# piezo-driver_v0_1-R001.net
KiCad netlist of a schematic drawn in EAGLE
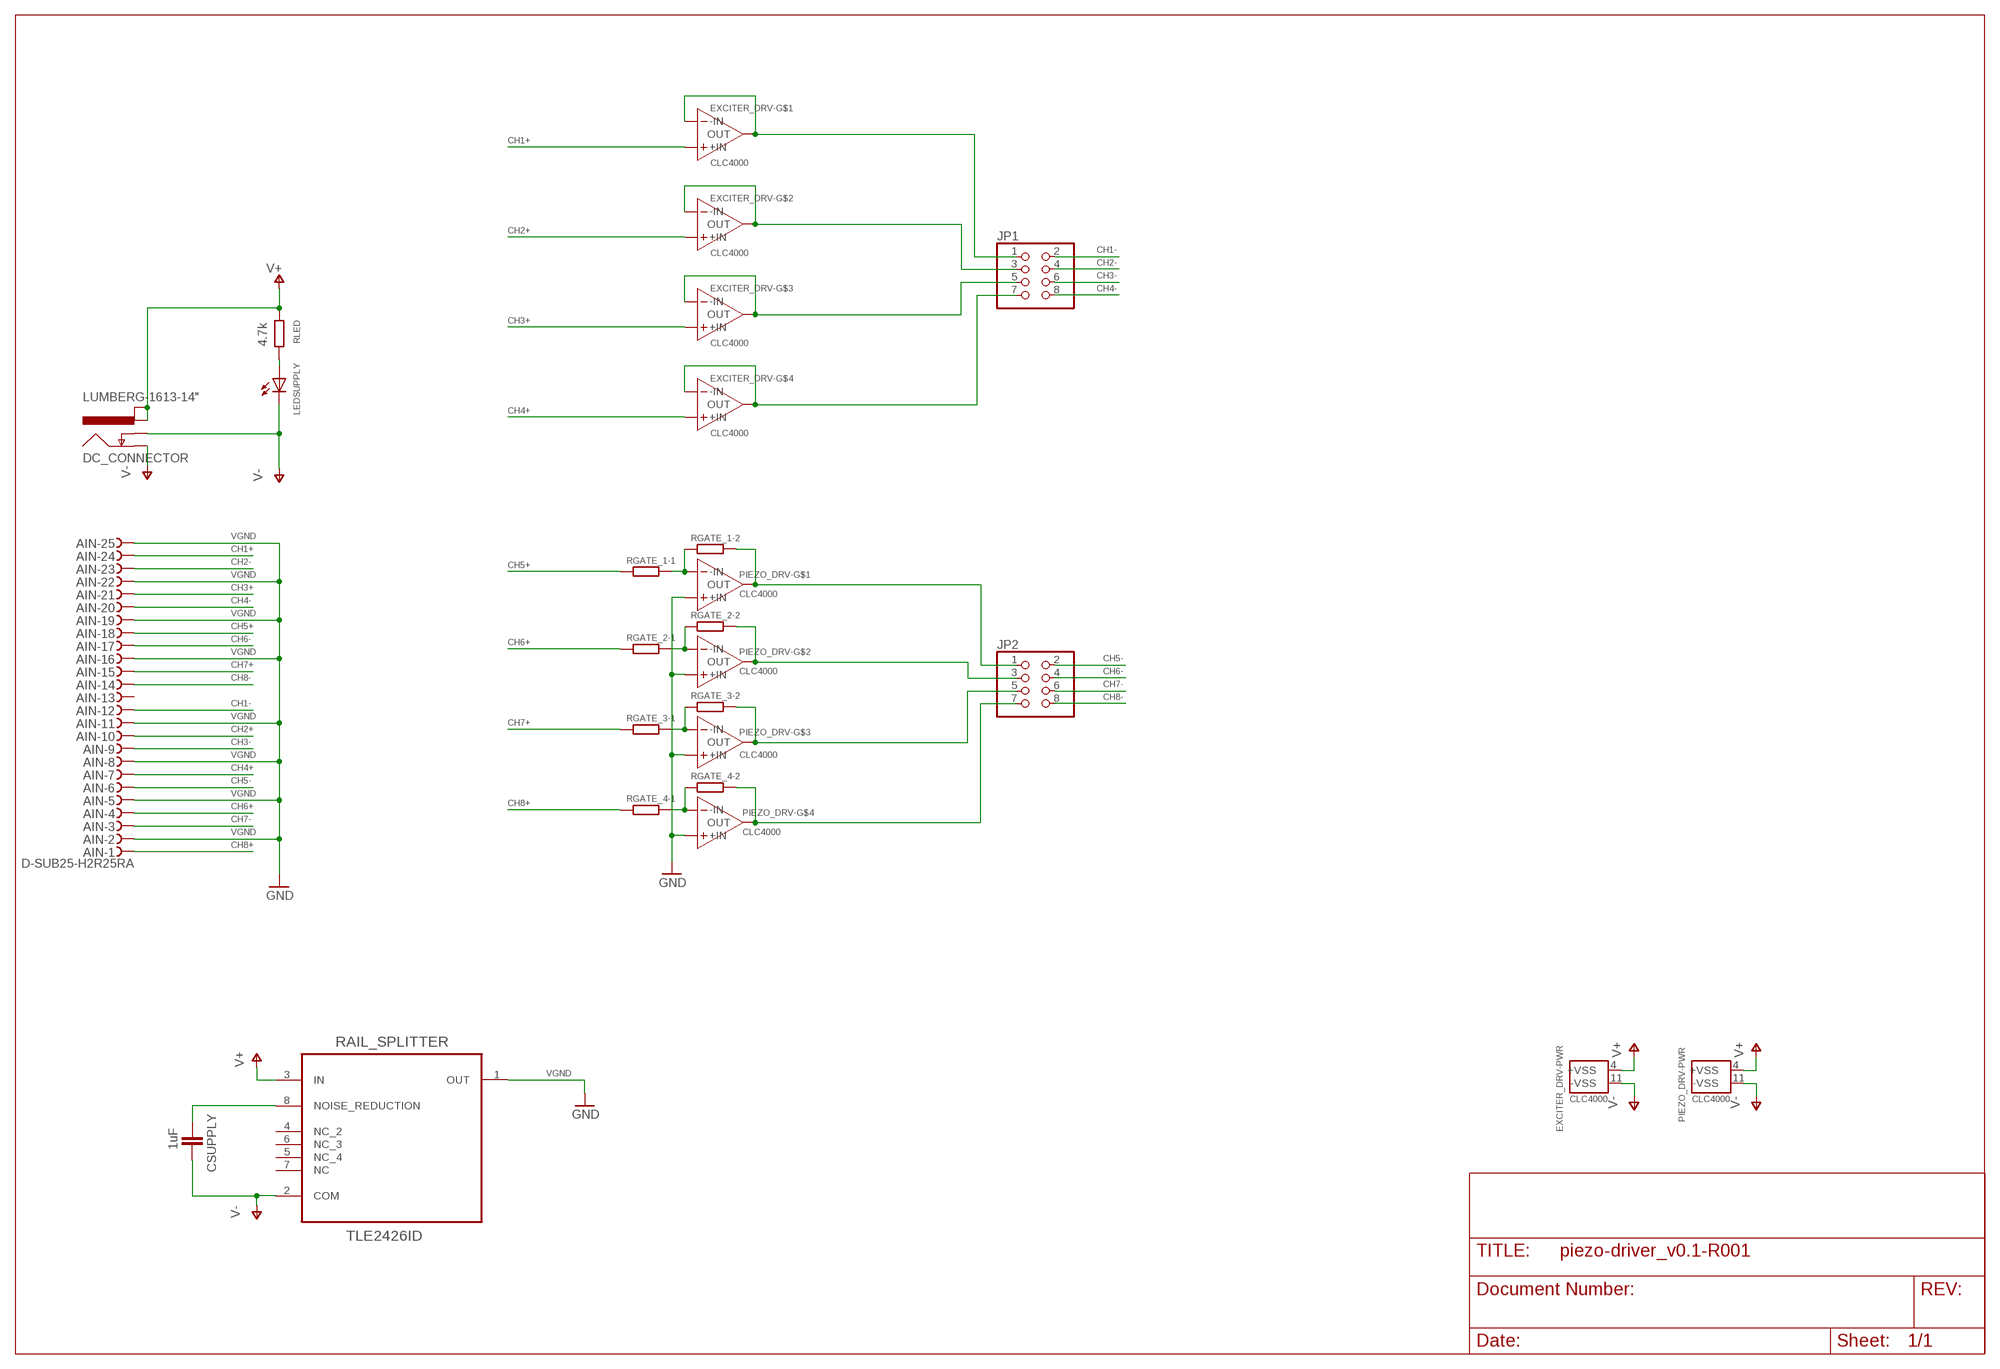
[diagram p0: schematic, sheet 1]

(export (version "E")
  (design (tool "Eeschema 10.0.6"))
  (components
    (comp (ref "AIN")
      (value "D-SUB25-H2R25RA")
      (footprint "eagle-import:H2R25RA")
      (libsource (lib "eagle-import") (part "D-SUB25-H2R25RA"))
    )
    (comp (ref "CSUPPLY")
      (value "1uF")
      (footprint "eagle-import:C0603")
      (libsource (lib "eagle-import") (part "C-EUC0603"))
    )
    (comp (ref "DC_CONNECTOR")
      (value "LUMBERG-1613-14\"")
      (footprint "eagle-import:LUMBERG-1613_14")
      (libsource (lib "eagle-import") (part "LUMBERG-1613-14{dblquote}"))
    )
    (comp (ref "EXCITER_DRV")
      (value "CLC4000")
      (footprint "eagle-import:SOIC-14")
      (libsource (lib "eagle-import") (part "CLC4000"))
    )
    (comp (ref "JP1")
      (value "PINHD-2X4/90")
      (footprint "eagle-import:2X04_90")
      (libsource (lib "eagle-import") (part "PINHD-2X4/90"))
    )
    (comp (ref "JP2")
      (value "PINHD-2X4/90")
      (footprint "eagle-import:2X04_90")
      (libsource (lib "eagle-import") (part "PINHD-2X4/90"))
    )
    (comp (ref "LEDSUPPLY")
      (value "LED3MM")
      (footprint "eagle-import:LED3MM")
      (libsource (lib "eagle-import") (part "LED3MM"))
    )
    (comp (ref "PIEZO_DRV")
      (value "CLC4000")
      (footprint "eagle-import:SOIC-14")
      (libsource (lib "eagle-import") (part "CLC4000"))
    )
    (comp (ref "RAIL_SPLITTER")
      (value "TLE2426ID")
      (footprint "eagle-import:SOIC127P600X175-8N")
      (libsource (lib "eagle-import") (part "TLE2426ID"))
    )
    (comp (ref "RGATE_1-1")
      (value "R-EU_R0805")
      (footprint "eagle-import:R0805")
      (libsource (lib "eagle-import") (part "R-EU_R0805"))
    )
    (comp (ref "RGATE_1-2")
      (value "R-EU_R0805")
      (footprint "eagle-import:R0805")
      (libsource (lib "eagle-import") (part "R-EU_R0805"))
    )
    (comp (ref "RGATE_2-1")
      (value "R-EU_R0805")
      (footprint "eagle-import:R0805")
      (libsource (lib "eagle-import") (part "R-EU_R0805"))
    )
    (comp (ref "RGATE_2-2")
      (value "R-EU_R0805")
      (footprint "eagle-import:R0805")
      (libsource (lib "eagle-import") (part "R-EU_R0805"))
    )
    (comp (ref "RGATE_3-1")
      (value "R-EU_R0805")
      (footprint "eagle-import:R0805")
      (libsource (lib "eagle-import") (part "R-EU_R0805"))
    )
    (comp (ref "RGATE_3-2")
      (value "R-EU_R0805")
      (footprint "eagle-import:R0805")
      (libsource (lib "eagle-import") (part "R-EU_R0805"))
    )
    (comp (ref "RGATE_4-1")
      (value "R-EU_R0805")
      (footprint "eagle-import:R0805")
      (libsource (lib "eagle-import") (part "R-EU_R0805"))
    )
    (comp (ref "RGATE_4-2")
      (value "R-EU_R0805")
      (footprint "eagle-import:R0805")
      (libsource (lib "eagle-import") (part "R-EU_R0805"))
    )
    (comp (ref "RLED")
      (value "4.7k")
      (footprint "eagle-import:R0805")
      (libsource (lib "eagle-import") (part "R-EU_R0805"))
    )
  )
  (nets
    (net (code "1") (name "/CH1+") (class "Default")
      (node (ref "AIN") (pin "24") (pinfunction "F_24") (pintype "passive"))
      (node (ref "EXCITER_DRV") (pin "3") (pinfunction "+IN_3") (pintype "bidirectional"))
    )
    (net (code "2") (name "/CH1-") (class "Default")
      (node (ref "AIN") (pin "12") (pinfunction "F_12") (pintype "passive"))
      (node (ref "JP1") (pin "2") (pinfunction "2_2") (pintype "passive"))
    )
    (net (code "3") (name "/CH2+") (class "Default")
      (node (ref "AIN") (pin "10") (pinfunction "F_10") (pintype "passive"))
      (node (ref "EXCITER_DRV") (pin "5") (pinfunction "+IN_5") (pintype "bidirectional"))
    )
    (net (code "4") (name "/CH2-") (class "Default")
      (node (ref "AIN") (pin "23") (pinfunction "F_23") (pintype "passive"))
      (node (ref "JP1") (pin "4") (pinfunction "4_4") (pintype "passive"))
    )
    (net (code "5") (name "/CH3+") (class "Default")
      (node (ref "AIN") (pin "21") (pinfunction "F_21") (pintype "passive"))
      (node (ref "EXCITER_DRV") (pin "10") (pinfunction "+IN_10") (pintype "bidirectional"))
    )
    (net (code "6") (name "/CH3-") (class "Default")
      (node (ref "AIN") (pin "9") (pinfunction "F_9") (pintype "passive"))
      (node (ref "JP1") (pin "6") (pinfunction "6_6") (pintype "passive"))
    )
    (net (code "7") (name "/CH4+") (class "Default")
      (node (ref "AIN") (pin "7") (pinfunction "F_7") (pintype "passive"))
      (node (ref "EXCITER_DRV") (pin "12") (pinfunction "+IN_12") (pintype "bidirectional"))
    )
    (net (code "8") (name "/CH4-") (class "Default")
      (node (ref "AIN") (pin "20") (pinfunction "F_20") (pintype "passive"))
      (node (ref "JP1") (pin "8") (pinfunction "8_8") (pintype "passive"))
    )
    (net (code "9") (name "/CH5+") (class "Default")
      (node (ref "AIN") (pin "18") (pinfunction "F_18") (pintype "passive"))
      (node (ref "RGATE_1-1") (pin "1") (pinfunction "1_1") (pintype "passive"))
    )
    (net (code "10") (name "/CH5-") (class "Default")
      (node (ref "AIN") (pin "6") (pinfunction "F_6") (pintype "passive"))
      (node (ref "JP2") (pin "2") (pinfunction "2_2") (pintype "passive"))
    )
    (net (code "11") (name "/CH6+") (class "Default")
      (node (ref "AIN") (pin "4") (pinfunction "F_4") (pintype "passive"))
      (node (ref "RGATE_2-1") (pin "1") (pinfunction "1_1") (pintype "passive"))
    )
    (net (code "12") (name "/CH6-") (class "Default")
      (node (ref "AIN") (pin "17") (pinfunction "F_17") (pintype "passive"))
      (node (ref "JP2") (pin "4") (pinfunction "4_4") (pintype "passive"))
    )
    (net (code "13") (name "/CH7+") (class "Default")
      (node (ref "AIN") (pin "15") (pinfunction "F_15") (pintype "passive"))
      (node (ref "RGATE_3-1") (pin "1") (pinfunction "1_1") (pintype "passive"))
    )
    (net (code "14") (name "/CH7-") (class "Default")
      (node (ref "AIN") (pin "3") (pinfunction "F_3") (pintype "passive"))
      (node (ref "JP2") (pin "6") (pinfunction "6_6") (pintype "passive"))
    )
    (net (code "15") (name "/CH8+") (class "Default")
      (node (ref "AIN") (pin "1") (pinfunction "F_1") (pintype "passive"))
      (node (ref "RGATE_4-1") (pin "1") (pinfunction "1_1") (pintype "passive"))
    )
    (net (code "16") (name "/CH8-") (class "Default")
      (node (ref "AIN") (pin "14") (pinfunction "F_14") (pintype "passive"))
      (node (ref "JP2") (pin "8") (pinfunction "8_8") (pintype "passive"))
    )
    (net (code "17") (name "GND") (class "Default")
      (node (ref "AIN") (pin "11") (pinfunction "F_11") (pintype "passive"))
      (node (ref "AIN") (pin "16") (pinfunction "F_16") (pintype "passive"))
      (node (ref "AIN") (pin "19") (pinfunction "F_19") (pintype "passive"))
      (node (ref "AIN") (pin "2") (pinfunction "F_2") (pintype "passive"))
      (node (ref "AIN") (pin "22") (pinfunction "F_22") (pintype "passive"))
      (node (ref "AIN") (pin "25") (pinfunction "F_25") (pintype "passive"))
      (node (ref "AIN") (pin "5") (pinfunction "F_5") (pintype "passive"))
      (node (ref "AIN") (pin "8") (pinfunction "F_8") (pintype "passive"))
      (node (ref "PIEZO_DRV") (pin "10") (pinfunction "+IN_10") (pintype "bidirectional"))
      (node (ref "PIEZO_DRV") (pin "12") (pinfunction "+IN_12") (pintype "bidirectional"))
      (node (ref "PIEZO_DRV") (pin "3") (pinfunction "+IN_3") (pintype "bidirectional"))
      (node (ref "PIEZO_DRV") (pin "5") (pinfunction "+IN_5") (pintype "bidirectional"))
      (node (ref "RAIL_SPLITTER") (pin "1") (pinfunction "OUT_1") (pintype "output"))
    )
    (net (code "18") (name "Net-(EXCITER_DRVA--IN)") (class "Default")
      (node (ref "EXCITER_DRV") (pin "1") (pinfunction "OUT_1") (pintype "bidirectional"))
      (node (ref "EXCITER_DRV") (pin "2") (pinfunction "-IN_2") (pintype "bidirectional"))
      (node (ref "JP1") (pin "1") (pinfunction "1_1") (pintype "passive"))
    )
    (net (code "19") (name "Net-(EXCITER_DRVB--IN)") (class "Default")
      (node (ref "EXCITER_DRV") (pin "6") (pinfunction "-IN_6") (pintype "bidirectional"))
      (node (ref "EXCITER_DRV") (pin "7") (pinfunction "OUT_7") (pintype "bidirectional"))
      (node (ref "JP1") (pin "3") (pinfunction "3_3") (pintype "passive"))
    )
    (net (code "20") (name "Net-(EXCITER_DRVC--IN)") (class "Default")
      (node (ref "EXCITER_DRV") (pin "8") (pinfunction "OUT_8") (pintype "bidirectional"))
      (node (ref "EXCITER_DRV") (pin "9") (pinfunction "-IN_9") (pintype "bidirectional"))
      (node (ref "JP1") (pin "5") (pinfunction "5_5") (pintype "passive"))
    )
    (net (code "21") (name "Net-(EXCITER_DRVD--IN)") (class "Default")
      (node (ref "EXCITER_DRV") (pin "13") (pinfunction "-IN_13") (pintype "bidirectional"))
      (node (ref "EXCITER_DRV") (pin "14") (pinfunction "OUT_14") (pintype "bidirectional"))
      (node (ref "JP1") (pin "7") (pinfunction "7_7") (pintype "passive"))
    )
    (net (code "22") (name "Net-(LEDSUPPLY-PadA)") (class "Default")
      (node (ref "LEDSUPPLY") (pin "A") (pinfunction "A_A") (pintype "passive"))
      (node (ref "RLED") (pin "1") (pinfunction "1_1") (pintype "passive"))
    )
    (net (code "23") (name "Net-(PIEZO_DRVA--IN)") (class "Default")
      (node (ref "PIEZO_DRV") (pin "2") (pinfunction "-IN_2") (pintype "bidirectional"))
      (node (ref "RGATE_1-1") (pin "2") (pinfunction "2_2") (pintype "passive"))
      (node (ref "RGATE_1-2") (pin "1") (pinfunction "1_1") (pintype "passive"))
    )
    (net (code "24") (name "Net-(PIEZO_DRVA-OUT)") (class "Default")
      (node (ref "JP2") (pin "1") (pinfunction "1_1") (pintype "passive"))
      (node (ref "PIEZO_DRV") (pin "1") (pinfunction "OUT_1") (pintype "bidirectional"))
      (node (ref "RGATE_1-2") (pin "2") (pinfunction "2_2") (pintype "passive"))
    )
    (net (code "25") (name "Net-(PIEZO_DRVB--IN)") (class "Default")
      (node (ref "PIEZO_DRV") (pin "6") (pinfunction "-IN_6") (pintype "bidirectional"))
      (node (ref "RGATE_2-1") (pin "2") (pinfunction "2_2") (pintype "passive"))
      (node (ref "RGATE_2-2") (pin "1") (pinfunction "1_1") (pintype "passive"))
    )
    (net (code "26") (name "Net-(PIEZO_DRVB-OUT)") (class "Default")
      (node (ref "JP2") (pin "3") (pinfunction "3_3") (pintype "passive"))
      (node (ref "PIEZO_DRV") (pin "7") (pinfunction "OUT_7") (pintype "bidirectional"))
      (node (ref "RGATE_2-2") (pin "2") (pinfunction "2_2") (pintype "passive"))
    )
    (net (code "27") (name "Net-(PIEZO_DRVC--IN)") (class "Default")
      (node (ref "PIEZO_DRV") (pin "9") (pinfunction "-IN_9") (pintype "bidirectional"))
      (node (ref "RGATE_3-1") (pin "2") (pinfunction "2_2") (pintype "passive"))
      (node (ref "RGATE_3-2") (pin "1") (pinfunction "1_1") (pintype "passive"))
    )
    (net (code "28") (name "Net-(PIEZO_DRVC-OUT)") (class "Default")
      (node (ref "JP2") (pin "5") (pinfunction "5_5") (pintype "passive"))
      (node (ref "PIEZO_DRV") (pin "8") (pinfunction "OUT_8") (pintype "bidirectional"))
      (node (ref "RGATE_3-2") (pin "2") (pinfunction "2_2") (pintype "passive"))
    )
    (net (code "29") (name "Net-(PIEZO_DRVD--IN)") (class "Default")
      (node (ref "PIEZO_DRV") (pin "13") (pinfunction "-IN_13") (pintype "bidirectional"))
      (node (ref "RGATE_4-1") (pin "2") (pinfunction "2_2") (pintype "passive"))
      (node (ref "RGATE_4-2") (pin "1") (pinfunction "1_1") (pintype "passive"))
    )
    (net (code "30") (name "Net-(PIEZO_DRVD-OUT)") (class "Default")
      (node (ref "JP2") (pin "7") (pinfunction "7_7") (pintype "passive"))
      (node (ref "PIEZO_DRV") (pin "14") (pinfunction "OUT_14") (pintype "bidirectional"))
      (node (ref "RGATE_4-2") (pin "2") (pinfunction "2_2") (pintype "passive"))
    )
    (net (code "31") (name "Net-(RAIL_SPLITTER-NOISE_REDUCTION)") (class "Default")
      (node (ref "CSUPPLY") (pin "1") (pinfunction "1_1") (pintype "passive"))
      (node (ref "RAIL_SPLITTER") (pin "8") (pinfunction "NOISE_REDUCTION_8") (pintype "passive"))
    )
    (net (code "32") (name "V+") (class "Default")
      (node (ref "DC_CONNECTOR") (pin "3") (pinfunction "PWR_1_3") (pintype "power_in"))
      (node (ref "DC_CONNECTOR") (pin "4") (pinfunction "PWR_2_4") (pintype "power_in"))
      (node (ref "EXCITER_DRV") (pin "4") (pinfunction "+VSS_4") (pintype "power_in"))
      (node (ref "PIEZO_DRV") (pin "4") (pinfunction "+VSS_4") (pintype "power_in"))
      (node (ref "RAIL_SPLITTER") (pin "3") (pinfunction "IN_3") (pintype "input"))
      (node (ref "RLED") (pin "2") (pinfunction "2_2") (pintype "passive"))
    )
    (net (code "33") (name "V-") (class "Default")
      (node (ref "CSUPPLY") (pin "2") (pinfunction "2_2") (pintype "passive"))
      (node (ref "DC_CONNECTOR") (pin "1") (pinfunction "GND_1") (pintype "power_in"))
      (node (ref "DC_CONNECTOR") (pin "2") (pinfunction "GND_INS_2") (pintype "power_in"))
      (node (ref "EXCITER_DRV") (pin "11") (pinfunction "-VSS_11") (pintype "power_in"))
      (node (ref "LEDSUPPLY") (pin "K") (pinfunction "C_K") (pintype "passive"))
      (node (ref "PIEZO_DRV") (pin "11") (pinfunction "-VSS_11") (pintype "power_in"))
      (node (ref "RAIL_SPLITTER") (pin "2") (pinfunction "COM_2") (pintype "passive"))
    )
    (net (code "34") (name "unconnected-(AINE-F-Pad13)") (class "Default")
      (node (ref "AIN") (pin "13") (pinfunction "F_13") (pintype "passive"))
    )
    (net (code "35") (name "unconnected-(RAIL_SPLITTER-NC-Pad7)") (class "Default")
      (node (ref "RAIL_SPLITTER") (pin "7") (pinfunction "NC_7") (pintype "no_connect"))
    )
    (net (code "36") (name "unconnected-(RAIL_SPLITTER-NC_2-Pad4)") (class "Default")
      (node (ref "RAIL_SPLITTER") (pin "4") (pinfunction "NC_2_4") (pintype "no_connect"))
    )
    (net (code "37") (name "unconnected-(RAIL_SPLITTER-NC_3-Pad6)") (class "Default")
      (node (ref "RAIL_SPLITTER") (pin "6") (pinfunction "NC_3_6") (pintype "no_connect"))
    )
    (net (code "38") (name "unconnected-(RAIL_SPLITTER-NC_4-Pad5)") (class "Default")
      (node (ref "RAIL_SPLITTER") (pin "5") (pinfunction "NC_4_5") (pintype "no_connect"))
    )
  )
)
